# Access_Control_USB_Hub_Switch.net
KiCad netlist of a schematic drawn in EasyEDA Pro
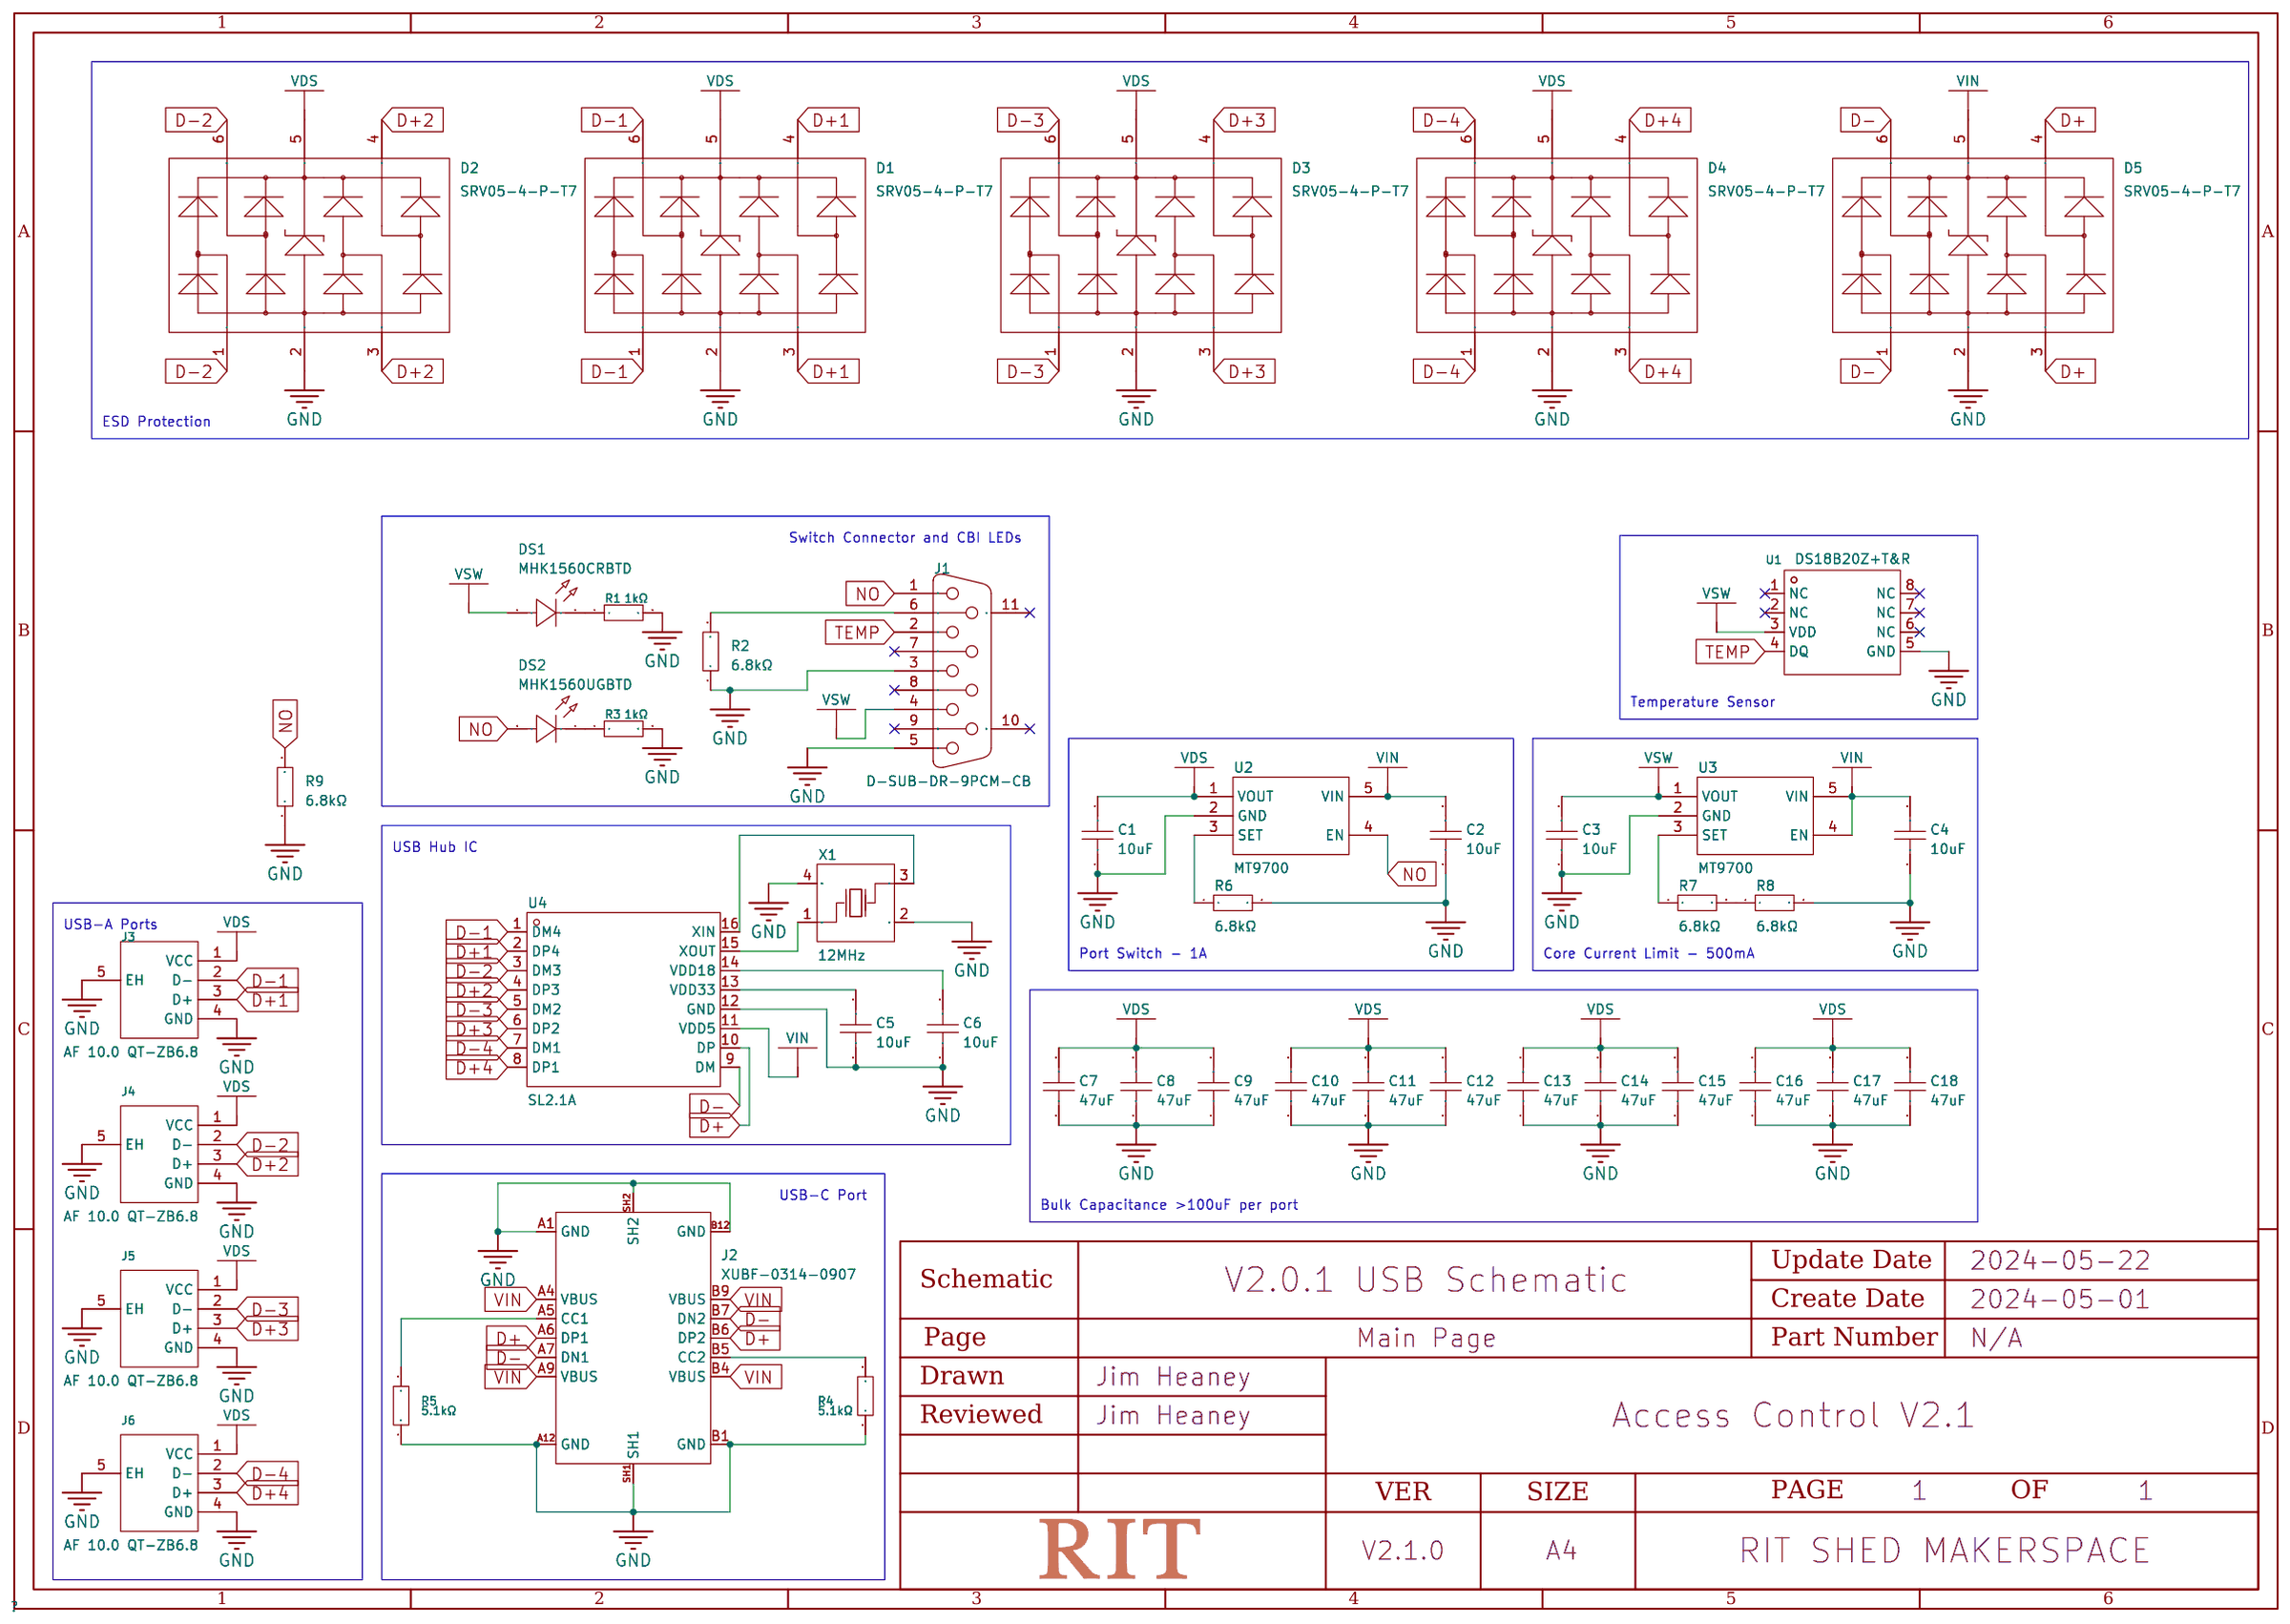
[diagram p0: schematic sheet]

(export (version "E")
  (design (tool "Eeschema 10.0.6"))
  (components
    (comp (ref "C1")
      (value "10uF")
      (footprint "easyedapro:C0603")
      (fields
        (field (name "Manufacturer Part") "CL10A106MA8NRNC")
        (field (name "Manufacturer") "SAMSUNG(三星)")
      )
      (libsource (lib "easyedapro") (part "CL10A106MA8NRNC"))
    )
    (comp (ref "C2")
      (value "10uF")
      (footprint "easyedapro:C0603")
      (fields
        (field (name "Manufacturer Part") "CL10A106MA8NRNC")
        (field (name "Manufacturer") "SAMSUNG(三星)")
      )
      (libsource (lib "easyedapro") (part "CL10A106MA8NRNC"))
    )
    (comp (ref "C3")
      (value "10uF")
      (footprint "easyedapro:C0603")
      (fields
        (field (name "Manufacturer Part") "CL10A106MA8NRNC")
        (field (name "Manufacturer") "SAMSUNG(三星)")
      )
      (libsource (lib "easyedapro") (part "CL10A106MA8NRNC"))
    )
    (comp (ref "C4")
      (value "10uF")
      (footprint "easyedapro:C0603")
      (fields
        (field (name "Manufacturer Part") "CL10A106MA8NRNC")
        (field (name "Manufacturer") "SAMSUNG(三星)")
      )
      (libsource (lib "easyedapro") (part "CL10A106MA8NRNC"))
    )
    (comp (ref "C5")
      (value "10uF")
      (footprint "easyedapro:C0603")
      (fields
        (field (name "Manufacturer Part") "CL10A106MA8NRNC")
        (field (name "Manufacturer") "SAMSUNG(三星)")
      )
      (libsource (lib "easyedapro") (part "CL10A106MA8NRNC"))
    )
    (comp (ref "C6")
      (value "10uF")
      (footprint "easyedapro:C0603")
      (fields
        (field (name "Manufacturer Part") "CL10A106MA8NRNC")
        (field (name "Manufacturer") "SAMSUNG(三星)")
      )
      (libsource (lib "easyedapro") (part "CL10A106MA8NRNC"))
    )
    (comp (ref "C7")
      (value "47uF")
      (footprint "easyedapro:C1206")
      (fields
        (field (name "Manufacturer Part") "CL31A476MPHNNNE")
        (field (name "Manufacturer") "SAMSUNG(三星)")
        (field (name "Tolerance") "±20%")
      )
      (libsource (lib "easyedapro") (part "CL31A476MPHNNNE"))
    )
    (comp (ref "C8")
      (value "47uF")
      (footprint "easyedapro:C1206")
      (fields
        (field (name "Manufacturer Part") "CL31A476MPHNNNE")
        (field (name "Manufacturer") "SAMSUNG(三星)")
        (field (name "Tolerance") "±20%")
      )
      (libsource (lib "easyedapro") (part "CL31A476MPHNNNE"))
    )
    (comp (ref "C9")
      (value "47uF")
      (footprint "easyedapro:C1206")
      (fields
        (field (name "Manufacturer Part") "CL31A476MPHNNNE")
        (field (name "Manufacturer") "SAMSUNG(三星)")
        (field (name "Tolerance") "±20%")
      )
      (libsource (lib "easyedapro") (part "CL31A476MPHNNNE"))
    )
    (comp (ref "C10")
      (value "47uF")
      (footprint "easyedapro:C1206")
      (fields
        (field (name "Manufacturer Part") "CL31A476MPHNNNE")
        (field (name "Manufacturer") "SAMSUNG(三星)")
        (field (name "Tolerance") "±20%")
      )
      (libsource (lib "easyedapro") (part "CL31A476MPHNNNE"))
    )
    (comp (ref "C11")
      (value "47uF")
      (footprint "easyedapro:C1206")
      (fields
        (field (name "Manufacturer Part") "CL31A476MPHNNNE")
        (field (name "Manufacturer") "SAMSUNG(三星)")
        (field (name "Tolerance") "±20%")
      )
      (libsource (lib "easyedapro") (part "CL31A476MPHNNNE"))
    )
    (comp (ref "C12")
      (value "47uF")
      (footprint "easyedapro:C1206")
      (fields
        (field (name "Manufacturer Part") "CL31A476MPHNNNE")
        (field (name "Manufacturer") "SAMSUNG(三星)")
        (field (name "Tolerance") "±20%")
      )
      (libsource (lib "easyedapro") (part "CL31A476MPHNNNE"))
    )
    (comp (ref "C13")
      (value "47uF")
      (footprint "easyedapro:C1206")
      (fields
        (field (name "Manufacturer Part") "CL31A476MPHNNNE")
        (field (name "Manufacturer") "SAMSUNG(三星)")
        (field (name "Tolerance") "±20%")
      )
      (libsource (lib "easyedapro") (part "CL31A476MPHNNNE"))
    )
    (comp (ref "C14")
      (value "47uF")
      (footprint "easyedapro:C1206")
      (fields
        (field (name "Manufacturer Part") "CL31A476MPHNNNE")
        (field (name "Manufacturer") "SAMSUNG(三星)")
        (field (name "Tolerance") "±20%")
      )
      (libsource (lib "easyedapro") (part "CL31A476MPHNNNE"))
    )
    (comp (ref "C15")
      (value "47uF")
      (footprint "easyedapro:C1206")
      (fields
        (field (name "Manufacturer Part") "CL31A476MPHNNNE")
        (field (name "Manufacturer") "SAMSUNG(三星)")
        (field (name "Tolerance") "±20%")
      )
      (libsource (lib "easyedapro") (part "CL31A476MPHNNNE"))
    )
    (comp (ref "C16")
      (value "47uF")
      (footprint "easyedapro:C1206")
      (fields
        (field (name "Manufacturer Part") "CL31A476MPHNNNE")
        (field (name "Manufacturer") "SAMSUNG(三星)")
        (field (name "Tolerance") "±20%")
      )
      (libsource (lib "easyedapro") (part "CL31A476MPHNNNE"))
    )
    (comp (ref "C17")
      (value "47uF")
      (footprint "easyedapro:C1206")
      (fields
        (field (name "Manufacturer Part") "CL31A476MPHNNNE")
        (field (name "Manufacturer") "SAMSUNG(三星)")
        (field (name "Tolerance") "±20%")
      )
      (libsource (lib "easyedapro") (part "CL31A476MPHNNNE"))
    )
    (comp (ref "C18")
      (value "47uF")
      (footprint "easyedapro:C1206")
      (fields
        (field (name "Manufacturer Part") "CL31A476MPHNNNE")
        (field (name "Manufacturer") "SAMSUNG(三星)")
        (field (name "Tolerance") "±20%")
      )
      (libsource (lib "easyedapro") (part "CL31A476MPHNNNE"))
    )
    (comp (ref "D1")
      (value "SRV05-4-P-T7")
      (footprint "easyedapro:SOT-23-6_L2.9-W1.6-P0.95-LS2.8-BR")
      (fields (field (name "Manufacturer") "PROTEK"))
      (libsource (lib "easyedapro") (part "SRV05-4-P-T7"))
    )
    (comp (ref "D2")
      (value "SRV05-4-P-T7")
      (footprint "easyedapro:SOT-23-6_L2.9-W1.6-P0.95-LS2.8-BR")
      (fields (field (name "Manufacturer") "PROTEK"))
      (libsource (lib "easyedapro") (part "SRV05-4-P-T7"))
    )
    (comp (ref "D3")
      (value "SRV05-4-P-T7")
      (footprint "easyedapro:SOT-23-6_L2.9-W1.6-P0.95-LS2.8-BR")
      (fields (field (name "Manufacturer") "PROTEK"))
      (libsource (lib "easyedapro") (part "SRV05-4-P-T7"))
    )
    (comp (ref "D4")
      (value "SRV05-4-P-T7")
      (footprint "easyedapro:SOT-23-6_L2.9-W1.6-P0.95-LS2.8-BR")
      (fields (field (name "Manufacturer") "PROTEK"))
      (libsource (lib "easyedapro") (part "SRV05-4-P-T7"))
    )
    (comp (ref "D5")
      (value "SRV05-4-P-T7")
      (footprint "easyedapro:SOT-23-6_L2.9-W1.6-P0.95-LS2.8-BR")
      (fields (field (name "Manufacturer") "PROTEK"))
      (libsource (lib "easyedapro") (part "SRV05-4-P-T7"))
    )
    (comp (ref "DS1")
      (value "MHK1560CRBTD")
      (footprint "easyedapro:LED-TH_MHK1560UGBTD")
      (fields (field (name "Manufacturer") "MEIHUA(美华)"))
      (libsource (lib "easyedapro") (part "MHK1560CGBTD"))
    )
    (comp (ref "DS2")
      (value "MHK1560UGBTD")
      (footprint "easyedapro:LED-TH_MHK1560UGBTD")
      (fields (field (name "Manufacturer") "MEIHUA(美华)"))
      (libsource (lib "easyedapro") (part "MHK1560UGBTD"))
    )
    (comp (ref "J1")
      (value "D-SUB-DR-9PCM-CB")
      (footprint "easyedapro:DB9-TH_ID09S33E4GV00LF")
      (fields (field (name "Manufacturer") "XUNPU(讯普)"))
      (libsource (lib "easyedapro") (part "D-SUB-DR-9PCM-CB"))
    )
    (comp (ref "J2")
      (value "XUBF-0314-0907")
      (footprint "easyedapro:TYPE-C-TH_TYPE-C-14P-CC-2.6")
      (description "DIY of C7527703")
      (fields (field (name "Manufacturer") "Lian Xin Technology"))
      (libsource (lib "easyedapro") (part "TYPE-C 14P CC-2.6"))
    )
    (comp (ref "J3")
      (value "AF 10.0 QT-ZB6.8")
      (footprint "easyedapro:USB-A-SMD_AF-10.0-QT-ZB6.8")
      (fields (field (name "Manufacturer") "SHOU HAN(首韩)"))
      (libsource (lib "easyedapro") (part "AF 10.0 QT-ZB6.8"))
    )
    (comp (ref "J4")
      (value "AF 10.0 QT-ZB6.8")
      (footprint "easyedapro:USB-A-SMD_AF-10.0-QT-ZB6.8")
      (fields (field (name "Manufacturer") "SHOU HAN(首韩)"))
      (libsource (lib "easyedapro") (part "AF 10.0 QT-ZB6.8"))
    )
    (comp (ref "J5")
      (value "AF 10.0 QT-ZB6.8")
      (footprint "easyedapro:USB-A-SMD_AF-10.0-QT-ZB6.8")
      (fields (field (name "Manufacturer") "SHOU HAN(首韩)"))
      (libsource (lib "easyedapro") (part "AF 10.0 QT-ZB6.8"))
    )
    (comp (ref "J6")
      (value "AF 10.0 QT-ZB6.8")
      (footprint "easyedapro:USB-A-SMD_AF-10.0-QT-ZB6.8")
      (fields (field (name "Manufacturer") "SHOU HAN(首韩)"))
      (libsource (lib "easyedapro") (part "AF 10.0 QT-ZB6.8"))
    )
    (comp (ref "R1")
      (value "1kΩ")
      (footprint "easyedapro:R0603")
      (fields
        (field (name "Manufacturer Part") "0603WAF1001T5E")
        (field (name "Manufacturer") "UNI-ROYAL(厚声)")
      )
      (libsource (lib "easyedapro") (part "0603WAF1001T5E"))
    )
    (comp (ref "R2")
      (value "6.8kΩ")
      (footprint "easyedapro:R0603")
      (fields
        (field (name "Manufacturer Part") "0603WAF6801T5E")
        (field (name "Manufacturer") "UNI-ROYAL(厚声)")
      )
      (libsource (lib "easyedapro") (part "0603WAF6801T5E"))
    )
    (comp (ref "R3")
      (value "1kΩ")
      (footprint "easyedapro:R0603")
      (fields
        (field (name "Manufacturer Part") "0603WAF1001T5E")
        (field (name "Manufacturer") "UNI-ROYAL(厚声)")
      )
      (libsource (lib "easyedapro") (part "0603WAF1001T5E"))
    )
    (comp (ref "R4")
      (value "5.1kΩ")
      (footprint "easyedapro:R0603")
      (fields
        (field (name "Manufacturer Part") "0603WAF5101T5E")
        (field (name "Manufacturer") "UNI-ROYAL(厚声)")
      )
      (libsource (lib "easyedapro") (part "0603WAF5101T5E"))
    )
    (comp (ref "R5")
      (value "5.1kΩ")
      (footprint "easyedapro:R0603")
      (fields
        (field (name "Manufacturer Part") "0603WAF5101T5E")
        (field (name "Manufacturer") "UNI-ROYAL(厚声)")
      )
      (libsource (lib "easyedapro") (part "0603WAF5101T5E"))
    )
    (comp (ref "R6")
      (value "6.8kΩ")
      (footprint "easyedapro:R0603")
      (fields
        (field (name "Manufacturer Part") "0603WAF6801T5E")
        (field (name "Manufacturer") "UNI-ROYAL(厚声)")
      )
      (libsource (lib "easyedapro") (part "0603WAF6801T5E"))
    )
    (comp (ref "R7")
      (value "6.8kΩ")
      (footprint "easyedapro:R0603")
      (fields
        (field (name "Manufacturer Part") "0603WAF6801T5E")
        (field (name "Manufacturer") "UNI-ROYAL(厚声)")
      )
      (libsource (lib "easyedapro") (part "0603WAF6801T5E"))
    )
    (comp (ref "R8")
      (value "6.8kΩ")
      (footprint "easyedapro:R0603")
      (fields
        (field (name "Manufacturer Part") "0603WAF6801T5E")
        (field (name "Manufacturer") "UNI-ROYAL(厚声)")
      )
      (libsource (lib "easyedapro") (part "0603WAF6801T5E"))
    )
    (comp (ref "R9")
      (value "6.8kΩ")
      (footprint "easyedapro:R0603")
      (fields
        (field (name "Manufacturer Part") "0603WAF6801T5E")
        (field (name "Manufacturer") "UNI-ROYAL(厚声)")
      )
      (libsource (lib "easyedapro") (part "0603WAF6801T5E"))
    )
    (comp (ref "U1")
      (value "DS18B20Z+T&R")
      (footprint "easyedapro:SOIC-8_L4.9-W3.9-P1.27-LS6.0-BL")
      (description "Supply Voltage:3V~5.5V Supply Voltage:3V~5.5V")
      (fields (field (name "Manufacturer") "ADI(亚德诺)/MAXIM(美信)"))
      (libsource (lib "easyedapro") (part "DS18B20Z+T&amp;R"))
    )
    (comp (ref "U2")
      (value "MT9700")
      (footprint "easyedapro:SOT-23-5_L3.0-W1.7-P0.95-LS2.8-BR")
      (fields (field (name "Manufacturer") "西安航天民芯"))
      (libsource (lib "easyedapro") (part "MT9700"))
    )
    (comp (ref "U3")
      (value "MT9700")
      (footprint "easyedapro:SOT-23-5_L3.0-W1.7-P0.95-LS2.8-BR")
      (fields (field (name "Manufacturer") "西安航天民芯"))
      (libsource (lib "easyedapro") (part "MT9700"))
    )
    (comp (ref "U4")
      (value "SL2.1A")
      (footprint "easyedapro:SOP-16_L10.0-W3.9-P1.27-LS6.0-BL")
      (fields (field (name "Manufacturer") "CoreChips(和芯润德)"))
      (libsource (lib "easyedapro") (part "SL2.1A"))
    )
    (comp (ref "X1")
      (value "12MHz")
      (footprint "easyedapro:OSC-SMD_4P-L3.2-W2.5-BL")
      (fields (field (name "Manufacturer Part") "X322512MSB4SI") (field (name "Manufacturer") "YXC(扬兴晶振)"))
      (libsource (lib "easyedapro") (part "X322512MSB4SI"))
    )
  )
  (nets
    (net (code "1") (name "D+") (class "Default")
      (node (ref "D5") (pin "3") (pinfunction "3_3") (pintype "input"))
      (node (ref "D5") (pin "4") (pinfunction "4_4") (pintype "input"))
      (node (ref "J2") (pin "A6") (pinfunction "DP1_A6") (pintype "input"))
      (node (ref "J2") (pin "B6") (pinfunction "DP2_B6") (pintype "input"))
      (node (ref "U4") (pin "10") (pinfunction "DP_10") (pintype "input"))
    )
    (net (code "2") (name "D+1") (class "Default")
      (node (ref "D1") (pin "3") (pinfunction "3_3") (pintype "input"))
      (node (ref "D1") (pin "4") (pinfunction "4_4") (pintype "input"))
      (node (ref "J3") (pin "3") (pinfunction "D+_3") (pintype "input"))
      (node (ref "U4") (pin "2") (pinfunction "DP4_2") (pintype "input"))
    )
    (net (code "3") (name "D+2") (class "Default")
      (node (ref "D2") (pin "3") (pinfunction "3_3") (pintype "input"))
      (node (ref "D2") (pin "4") (pinfunction "4_4") (pintype "input"))
      (node (ref "J4") (pin "3") (pinfunction "D+_3") (pintype "input"))
      (node (ref "U4") (pin "4") (pinfunction "DP3_4") (pintype "input"))
    )
    (net (code "4") (name "D+3") (class "Default")
      (node (ref "D3") (pin "3") (pinfunction "3_3") (pintype "input"))
      (node (ref "D3") (pin "4") (pinfunction "4_4") (pintype "input"))
      (node (ref "J5") (pin "3") (pinfunction "D+_3") (pintype "input"))
      (node (ref "U4") (pin "6") (pinfunction "DP2_6") (pintype "input"))
    )
    (net (code "5") (name "D+4") (class "Default")
      (node (ref "D4") (pin "3") (pinfunction "3_3") (pintype "input"))
      (node (ref "D4") (pin "4") (pinfunction "4_4") (pintype "input"))
      (node (ref "J6") (pin "3") (pinfunction "D+_3") (pintype "input"))
      (node (ref "U4") (pin "8") (pinfunction "DP1_8") (pintype "input"))
    )
    (net (code "6") (name "D-") (class "Default")
      (node (ref "D5") (pin "1") (pinfunction "1_1") (pintype "input"))
      (node (ref "D5") (pin "6") (pinfunction "6_6") (pintype "input"))
      (node (ref "J2") (pin "A7") (pinfunction "DN1_A7") (pintype "input"))
      (node (ref "J2") (pin "B7") (pinfunction "DN2_B7") (pintype "input"))
      (node (ref "U4") (pin "9") (pinfunction "DM_9") (pintype "input"))
    )
    (net (code "7") (name "D-1") (class "Default")
      (node (ref "D1") (pin "1") (pinfunction "1_1") (pintype "input"))
      (node (ref "D1") (pin "6") (pinfunction "6_6") (pintype "input"))
      (node (ref "J3") (pin "2") (pinfunction "D-_2") (pintype "input"))
      (node (ref "U4") (pin "1") (pinfunction "DM4_1") (pintype "input"))
    )
    (net (code "8") (name "D-2") (class "Default")
      (node (ref "D2") (pin "1") (pinfunction "1_1") (pintype "input"))
      (node (ref "D2") (pin "6") (pinfunction "6_6") (pintype "input"))
      (node (ref "J4") (pin "2") (pinfunction "D-_2") (pintype "input"))
      (node (ref "U4") (pin "3") (pinfunction "DM3_3") (pintype "input"))
    )
    (net (code "9") (name "D-3") (class "Default")
      (node (ref "D3") (pin "1") (pinfunction "1_1") (pintype "input"))
      (node (ref "D3") (pin "6") (pinfunction "6_6") (pintype "input"))
      (node (ref "J5") (pin "2") (pinfunction "D-_2") (pintype "input"))
      (node (ref "U4") (pin "5") (pinfunction "DM2_5") (pintype "input"))
    )
    (net (code "10") (name "D-4") (class "Default")
      (node (ref "D4") (pin "1") (pinfunction "1_1") (pintype "input"))
      (node (ref "D4") (pin "6") (pinfunction "6_6") (pintype "input"))
      (node (ref "J6") (pin "2") (pinfunction "D-_2") (pintype "input"))
      (node (ref "U4") (pin "7") (pinfunction "DM1_7") (pintype "input"))
    )
    (net (code "11") (name "GND") (class "Default")
      (node (ref "C1") (pin "1") (pinfunction "1_1") (pintype "input"))
      (node (ref "C10") (pin "1") (pinfunction "1_1") (pintype "input"))
      (node (ref "C11") (pin "1") (pinfunction "1_1") (pintype "input"))
      (node (ref "C12") (pin "1") (pinfunction "1_1") (pintype "input"))
      (node (ref "C13") (pin "1") (pinfunction "1_1") (pintype "input"))
      (node (ref "C14") (pin "1") (pinfunction "1_1") (pintype "input"))
      (node (ref "C15") (pin "1") (pinfunction "1_1") (pintype "input"))
      (node (ref "C16") (pin "1") (pinfunction "1_1") (pintype "input"))
      (node (ref "C17") (pin "1") (pinfunction "1_1") (pintype "input"))
      (node (ref "C18") (pin "1") (pinfunction "1_1") (pintype "input"))
      (node (ref "C2") (pin "1") (pinfunction "1_1") (pintype "input"))
      (node (ref "C3") (pin "1") (pinfunction "1_1") (pintype "input"))
      (node (ref "C4") (pin "1") (pinfunction "1_1") (pintype "input"))
      (node (ref "C5") (pin "1") (pinfunction "1_1") (pintype "input"))
      (node (ref "C6") (pin "1") (pinfunction "1_1") (pintype "input"))
      (node (ref "C7") (pin "1") (pinfunction "1_1") (pintype "input"))
      (node (ref "C8") (pin "1") (pinfunction "1_1") (pintype "input"))
      (node (ref "C9") (pin "1") (pinfunction "1_1") (pintype "input"))
      (node (ref "D1") (pin "2") (pinfunction "2_2") (pintype "input"))
      (node (ref "D2") (pin "2") (pinfunction "2_2") (pintype "input"))
      (node (ref "D3") (pin "2") (pinfunction "2_2") (pintype "input"))
      (node (ref "D4") (pin "2") (pinfunction "2_2") (pintype "input"))
      (node (ref "D5") (pin "2") (pinfunction "2_2") (pintype "input"))
      (node (ref "J1") (pin "3") (pinfunction "3_3") (pintype "input"))
      (node (ref "J1") (pin "5") (pinfunction "5_5") (pintype "input"))
      (node (ref "J2") (pin "A1") (pinfunction "GND_A1") (pintype "input"))
      (node (ref "J2") (pin "A12") (pinfunction "GND_A12") (pintype "input"))
      (node (ref "J2") (pin "B1") (pinfunction "GND_B1") (pintype "input"))
      (node (ref "J2") (pin "B12") (pinfunction "GND_B12") (pintype "input"))
      (node (ref "J2") (pin "SH1") (pinfunction "SH1_SH1") (pintype "input"))
      (node (ref "J2") (pin "SH2") (pinfunction "SH2_SH2") (pintype "input"))
      (node (ref "J3") (pin "4") (pinfunction "GND_4") (pintype "input"))
      (node (ref "J3") (pin "5") (pinfunction "EH_5") (pintype "input"))
      (node (ref "J4") (pin "4") (pinfunction "GND_4") (pintype "input"))
      (node (ref "J4") (pin "5") (pinfunction "EH_5") (pintype "input"))
      (node (ref "J5") (pin "4") (pinfunction "GND_4") (pintype "input"))
      (node (ref "J5") (pin "5") (pinfunction "EH_5") (pintype "input"))
      (node (ref "J6") (pin "4") (pinfunction "GND_4") (pintype "input"))
      (node (ref "J6") (pin "5") (pinfunction "EH_5") (pintype "input"))
      (node (ref "R1") (pin "2") (pinfunction "2_2") (pintype "input"))
      (node (ref "R2") (pin "1") (pinfunction "1_1") (pintype "input"))
      (node (ref "R3") (pin "2") (pinfunction "2_2") (pintype "input"))
      (node (ref "R4") (pin "1") (pinfunction "1_1") (pintype "input"))
      (node (ref "R5") (pin "1") (pinfunction "1_1") (pintype "input"))
      (node (ref "R6") (pin "2") (pinfunction "2_2") (pintype "input"))
      (node (ref "R8") (pin "2") (pinfunction "2_2") (pintype "input"))
      (node (ref "R9") (pin "1") (pinfunction "1_1") (pintype "input"))
      (node (ref "U1") (pin "5") (pinfunction "GND_5") (pintype "input"))
      (node (ref "U2") (pin "2") (pinfunction "GND_2") (pintype "input"))
      (node (ref "U3") (pin "2") (pinfunction "GND_2") (pintype "input"))
      (node (ref "U4") (pin "12") (pinfunction "GND_12") (pintype "input"))
      (node (ref "X1") (pin "2") (pinfunction "GND_2") (pintype "input"))
      (node (ref "X1") (pin "4") (pinfunction "GND_4") (pintype "input"))
    )
    (net (code "12") (name "NO") (class "Default")
      (node (ref "DS2") (pin "2") (pinfunction "A_2") (pintype "unspecified"))
      (node (ref "J1") (pin "1") (pinfunction "1_1") (pintype "input"))
      (node (ref "R9") (pin "2") (pinfunction "2_2") (pintype "input"))
      (node (ref "U2") (pin "4") (pinfunction "EN_4") (pintype "input"))
    )
    (net (code "13") (name "Net-(DS1-K)") (class "Default")
      (node (ref "DS1") (pin "1") (pinfunction "K_1") (pintype "unspecified"))
      (node (ref "R1") (pin "1") (pinfunction "1_1") (pintype "input"))
    )
    (net (code "14") (name "Net-(DS2-K)") (class "Default")
      (node (ref "DS2") (pin "1") (pinfunction "K_1") (pintype "unspecified"))
      (node (ref "R3") (pin "1") (pinfunction "1_1") (pintype "input"))
    )
    (net (code "15") (name "Net-(J1-Pad6)") (class "Default")
      (node (ref "J1") (pin "6") (pinfunction "6_6") (pintype "input"))
      (node (ref "R2") (pin "2") (pinfunction "2_2") (pintype "input"))
    )
    (net (code "16") (name "Net-(J2-CC1)") (class "Default")
      (node (ref "J2") (pin "A5") (pinfunction "CC1_A5") (pintype "input"))
      (node (ref "R5") (pin "2") (pinfunction "2_2") (pintype "input"))
    )
    (net (code "17") (name "Net-(J2-CC2)") (class "Default")
      (node (ref "J2") (pin "B5") (pinfunction "CC2_B5") (pintype "input"))
      (node (ref "R4") (pin "2") (pinfunction "2_2") (pintype "input"))
    )
    (net (code "18") (name "Net-(R7-Pad2)") (class "Default")
      (node (ref "R7") (pin "2") (pinfunction "2_2") (pintype "input"))
      (node (ref "R8") (pin "1") (pinfunction "1_1") (pintype "input"))
    )
    (net (code "19") (name "Net-(U2-SET)") (class "Default")
      (node (ref "R6") (pin "1") (pinfunction "1_1") (pintype "input"))
      (node (ref "U2") (pin "3") (pinfunction "SET_3") (pintype "input"))
    )
    (net (code "20") (name "Net-(U3-SET)") (class "Default")
      (node (ref "R7") (pin "1") (pinfunction "1_1") (pintype "input"))
      (node (ref "U3") (pin "3") (pinfunction "SET_3") (pintype "input"))
    )
    (net (code "21") (name "Net-(U4-VDD18)") (class "Default")
      (node (ref "C6") (pin "2") (pinfunction "2_2") (pintype "input"))
      (node (ref "U4") (pin "14") (pinfunction "VDD18_14") (pintype "input"))
    )
    (net (code "22") (name "Net-(U4-VDD33)") (class "Default")
      (node (ref "C5") (pin "2") (pinfunction "2_2") (pintype "input"))
      (node (ref "U4") (pin "13") (pinfunction "VDD33_13") (pintype "input"))
    )
    (net (code "23") (name "Net-(U4-XIN)") (class "Default")
      (node (ref "U4") (pin "16") (pinfunction "XIN_16") (pintype "input"))
      (node (ref "X1") (pin "3") (pinfunction "OSC2_3") (pintype "input"))
    )
    (net (code "24") (name "Net-(U4-XOUT)") (class "Default")
      (node (ref "U4") (pin "15") (pinfunction "XOUT_15") (pintype "input"))
      (node (ref "X1") (pin "1") (pinfunction "OSC1_1") (pintype "input"))
    )
    (net (code "25") (name "TEMP") (class "Default")
      (node (ref "J1") (pin "2") (pinfunction "2_2") (pintype "input"))
      (node (ref "U1") (pin "4") (pinfunction "DQ_4") (pintype "input"))
    )
    (net (code "26") (name "VDS") (class "Default")
      (node (ref "C1") (pin "2") (pinfunction "2_2") (pintype "input"))
      (node (ref "C10") (pin "2") (pinfunction "2_2") (pintype "input"))
      (node (ref "C11") (pin "2") (pinfunction "2_2") (pintype "input"))
      (node (ref "C12") (pin "2") (pinfunction "2_2") (pintype "input"))
      (node (ref "C13") (pin "2") (pinfunction "2_2") (pintype "input"))
      (node (ref "C14") (pin "2") (pinfunction "2_2") (pintype "input"))
      (node (ref "C15") (pin "2") (pinfunction "2_2") (pintype "input"))
      (node (ref "C16") (pin "2") (pinfunction "2_2") (pintype "input"))
      (node (ref "C17") (pin "2") (pinfunction "2_2") (pintype "input"))
      (node (ref "C18") (pin "2") (pinfunction "2_2") (pintype "input"))
      (node (ref "C7") (pin "2") (pinfunction "2_2") (pintype "input"))
      (node (ref "C8") (pin "2") (pinfunction "2_2") (pintype "input"))
      (node (ref "C9") (pin "2") (pinfunction "2_2") (pintype "input"))
      (node (ref "D1") (pin "5") (pinfunction "5_5") (pintype "input"))
      (node (ref "D2") (pin "5") (pinfunction "5_5") (pintype "input"))
      (node (ref "D3") (pin "5") (pinfunction "5_5") (pintype "input"))
      (node (ref "D4") (pin "5") (pinfunction "5_5") (pintype "input"))
      (node (ref "J3") (pin "1") (pinfunction "VCC_1") (pintype "input"))
      (node (ref "J4") (pin "1") (pinfunction "VCC_1") (pintype "input"))
      (node (ref "J5") (pin "1") (pinfunction "VCC_1") (pintype "input"))
      (node (ref "J6") (pin "1") (pinfunction "VCC_1") (pintype "input"))
      (node (ref "U2") (pin "1") (pinfunction "VOUT_1") (pintype "input"))
    )
    (net (code "27") (name "VIN") (class "Default")
      (node (ref "C2") (pin "2") (pinfunction "2_2") (pintype "input"))
      (node (ref "C4") (pin "2") (pinfunction "2_2") (pintype "input"))
      (node (ref "D5") (pin "5") (pinfunction "5_5") (pintype "input"))
      (node (ref "J2") (pin "A4") (pinfunction "VBUS_A4") (pintype "input"))
      (node (ref "J2") (pin "A9") (pinfunction "VBUS_A9") (pintype "input"))
      (node (ref "J2") (pin "B4") (pinfunction "VBUS_B4") (pintype "input"))
      (node (ref "J2") (pin "B9") (pinfunction "VBUS_B9") (pintype "input"))
      (node (ref "U2") (pin "5") (pinfunction "VIN_5") (pintype "input"))
      (node (ref "U3") (pin "4") (pinfunction "EN_4") (pintype "input"))
      (node (ref "U3") (pin "5") (pinfunction "VIN_5") (pintype "input"))
      (node (ref "U4") (pin "11") (pinfunction "VDD5_11") (pintype "input"))
    )
    (net (code "28") (name "VSW") (class "Default")
      (node (ref "C3") (pin "2") (pinfunction "2_2") (pintype "input"))
      (node (ref "DS1") (pin "2") (pinfunction "A_2") (pintype "unspecified"))
      (node (ref "J1") (pin "4") (pinfunction "4_4") (pintype "input"))
      (node (ref "U1") (pin "3") (pinfunction "VDD_3") (pintype "input"))
      (node (ref "U3") (pin "1") (pinfunction "VOUT_1") (pintype "input"))
    )
    (net (code "29") (name "unconnected-(J1-MH1-Pad10)") (class "Default")
      (node (ref "J1") (pin "10") (pinfunction "MH1_10") (pintype "input+no_connect"))
    )
    (net (code "30") (name "unconnected-(J1-MH2-Pad11)") (class "Default")
      (node (ref "J1") (pin "11") (pinfunction "MH2_11") (pintype "input+no_connect"))
    )
    (net (code "31") (name "unconnected-(J1-Pad7)") (class "Default")
      (node (ref "J1") (pin "7") (pinfunction "7_7") (pintype "input+no_connect"))
    )
    (net (code "32") (name "unconnected-(J1-Pad8)") (class "Default")
      (node (ref "J1") (pin "8") (pinfunction "8_8") (pintype "input+no_connect"))
    )
    (net (code "33") (name "unconnected-(J1-Pad9)") (class "Default")
      (node (ref "J1") (pin "9") (pinfunction "9_9") (pintype "input+no_connect"))
    )
    (net (code "34") (name "unconnected-(U1-NC-Pad1)") (class "Default")
      (node (ref "U1") (pin "1") (pinfunction "NC_1") (pintype "input+no_connect"))
    )
    (net (code "35") (name "unconnected-(U1-NC-Pad2)") (class "Default")
      (node (ref "U1") (pin "2") (pinfunction "NC_2") (pintype "input+no_connect"))
    )
    (net (code "36") (name "unconnected-(U1-NC-Pad6)") (class "Default")
      (node (ref "U1") (pin "6") (pinfunction "NC_6") (pintype "input+no_connect"))
    )
    (net (code "37") (name "unconnected-(U1-NC-Pad7)") (class "Default")
      (node (ref "U1") (pin "7") (pinfunction "NC_7") (pintype "input+no_connect"))
    )
    (net (code "38") (name "unconnected-(U1-NC-Pad8)") (class "Default")
      (node (ref "U1") (pin "8") (pinfunction "NC_8") (pintype "input+no_connect"))
    )
  )
)
